# Pro_Micro_Micro_OLED.net
KiCad netlist of a schematic drawn in EAGLE
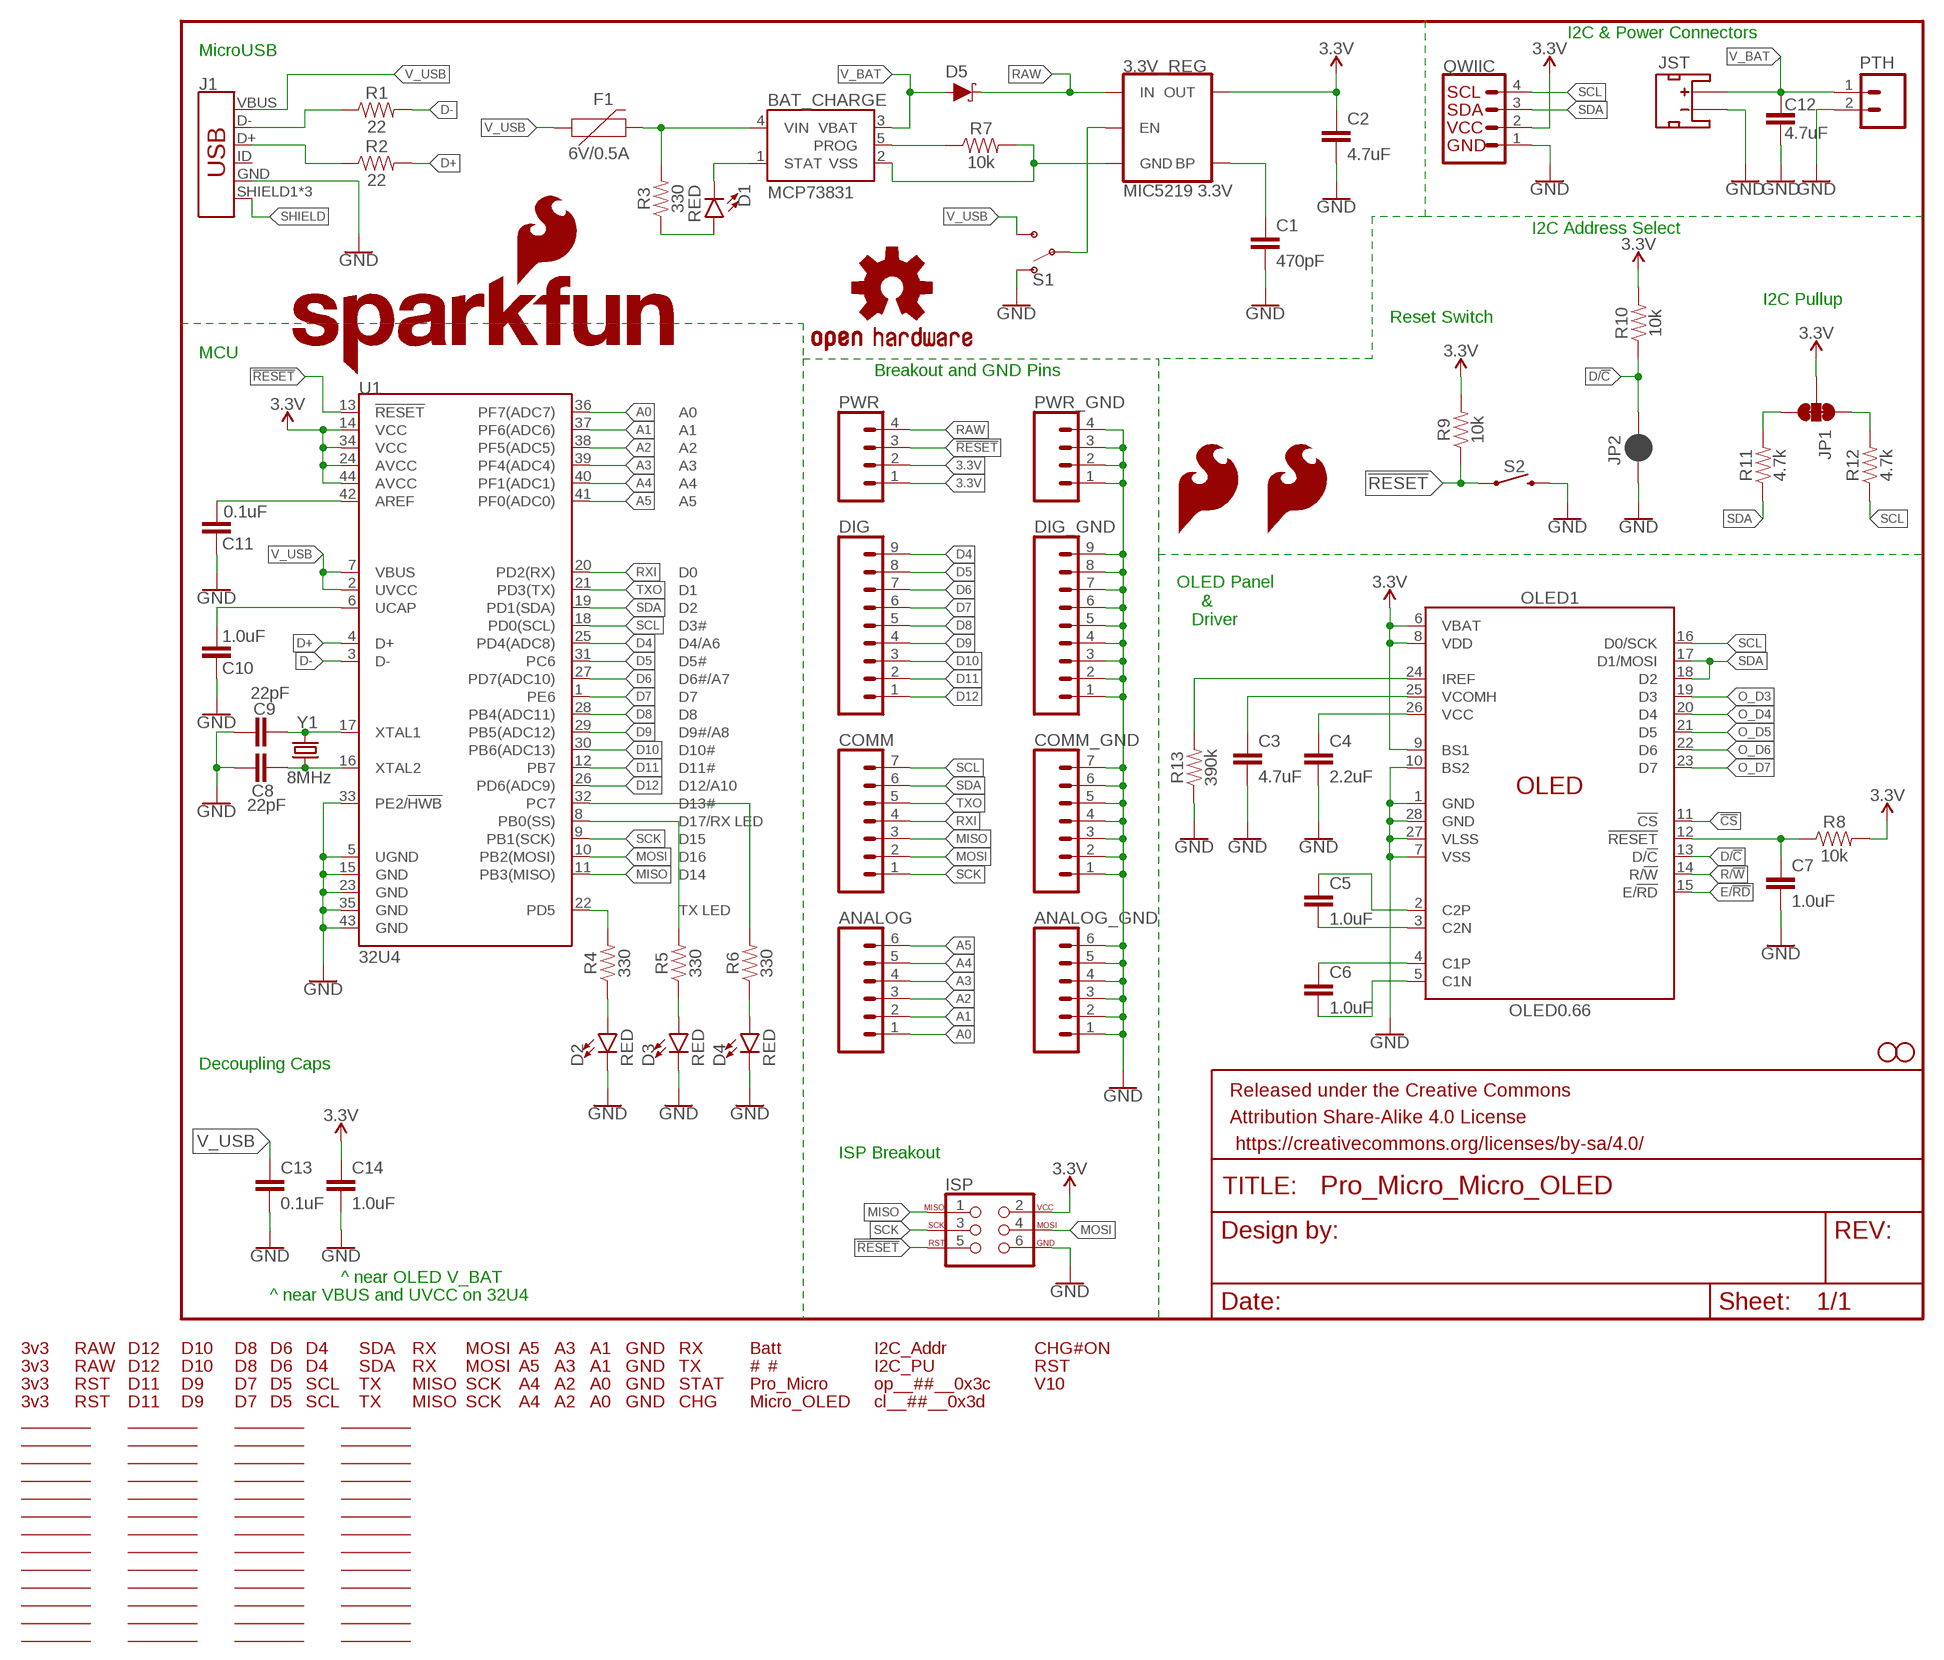
[diagram p0: schematic, sheet 1]

(export (version "E")
  (design (tool "Eeschema 10.0.6"))
  (components
    (comp (ref "3.3V_REG")
      (value "MIC5219 3.3V")
      (footprint "eagle-import:SOT23-5")
      (libsource (lib "eagle-import") (part "V_REG_MIC52193.3V"))
    )
    (comp (ref "ANALOG")
      (value "CONN_06NO_SILK_FEMALE_PTH")
      (footprint "eagle-import:1X06_NO_SILK")
      (libsource (lib "eagle-import") (part "CONN_06NO_SILK_FEMALE_PTH"))
    )
    (comp (ref "ANALOG_GND")
      (value "CONN_06NO_SILK_FEMALE_PTH")
      (footprint "eagle-import:1X06_NO_SILK")
      (libsource (lib "eagle-import") (part "CONN_06NO_SILK_FEMALE_PTH"))
    )
    (comp (ref "BAT_CHARGE")
      (value "MCP73831")
      (footprint "eagle-import:SOT23-5")
      (libsource (lib "eagle-import") (part "MCP73831"))
    )
    (comp (ref "C1")
      (value "470pF")
      (footprint "eagle-import:0603")
      (libsource (lib "eagle-import") (part "470PF-0603-50V-5%"))
    )
    (comp (ref "C2")
      (value "4.7uF")
      (footprint "eagle-import:1206")
      (libsource (lib "eagle-import") (part "4.7UF-1206-16V-(+80/-20%)"))
    )
    (comp (ref "C3")
      (value "4.7uF")
      (footprint "eagle-import:1206")
      (libsource (lib "eagle-import") (part "4.7UF-1206-16V-(+80/-20%)"))
    )
    (comp (ref "C4")
      (value "2.2uF")
      (footprint "eagle-import:0805")
      (libsource (lib "eagle-import") (part "2.2UF-0805-25V-(+80/-20%)"))
    )
    (comp (ref "C5")
      (value "1.0uF")
      (footprint "eagle-import:0805")
      (libsource (lib "eagle-import") (part "1.0UF-0805-25V-10%"))
    )
    (comp (ref "C6")
      (value "1.0uF")
      (footprint "eagle-import:0805")
      (libsource (lib "eagle-import") (part "1.0UF-0805-25V-10%"))
    )
    (comp (ref "C7")
      (value "1.0uF")
      (footprint "eagle-import:0603")
      (libsource (lib "eagle-import") (part "1.0UF-0603-16V-10%"))
    )
    (comp (ref "C8")
      (value "22pF")
      (footprint "eagle-import:0603")
      (libsource (lib "eagle-import") (part "22PF-0603-50V-5%"))
    )
    (comp (ref "C9")
      (value "22pF")
      (footprint "eagle-import:0603")
      (libsource (lib "eagle-import") (part "22PF-0603-50V-5%"))
    )
    (comp (ref "C10")
      (value "1.0uF")
      (footprint "eagle-import:0603")
      (libsource (lib "eagle-import") (part "1.0UF-0603-16V-10%"))
    )
    (comp (ref "C11")
      (value "0.1uF")
      (footprint "eagle-import:0603")
      (libsource (lib "eagle-import") (part "0.1UF-0603-25V-(+80/-20%)"))
    )
    (comp (ref "C12")
      (value "4.7uF")
      (footprint "eagle-import:1206")
      (libsource (lib "eagle-import") (part "4.7UF-1206-16V-(+80/-20%)"))
    )
    (comp (ref "C13")
      (value "0.1uF")
      (footprint "eagle-import:0603")
      (libsource (lib "eagle-import") (part "0.1UF-0603-25V-(+80/-20%)"))
    )
    (comp (ref "C14")
      (value "1.0uF")
      (footprint "eagle-import:0603")
      (libsource (lib "eagle-import") (part "1.0UF-0603-16V-10%"))
    )
    (comp (ref "COMM")
      (value "CONN_07NO_SILK")
      (footprint "eagle-import:1X07_NO_SILK")
      (libsource (lib "eagle-import") (part "CONN_07NO_SILK"))
    )
    (comp (ref "COMM_GND")
      (value "CONN_07NO_SILK")
      (footprint "eagle-import:1X07_NO_SILK")
      (libsource (lib "eagle-import") (part "CONN_07NO_SILK"))
    )
    (comp (ref "D1")
      (value "RED")
      (footprint "eagle-import:LED-0603")
      (libsource (lib "eagle-import") (part "LED-RED0603"))
    )
    (comp (ref "D2")
      (value "RED")
      (footprint "eagle-import:LED-0603")
      (libsource (lib "eagle-import") (part "LED-RED0603"))
    )
    (comp (ref "D3")
      (value "RED")
      (footprint "eagle-import:LED-0603")
      (libsource (lib "eagle-import") (part "LED-RED0603"))
    )
    (comp (ref "D4")
      (value "RED")
      (footprint "eagle-import:LED-0603")
      (libsource (lib "eagle-import") (part "LED-RED0603"))
    )
    (comp (ref "D5")
      (value "3A/40V/500mV")
      (footprint "eagle-import:SMA-DIODE")
      (libsource (lib "eagle-import") (part "DIODE-SCHOTTKY-B340A"))
    )
    (comp (ref "DIG")
      (value "CONN_09NO_SILK")
      (footprint "eagle-import:1X09_NO_SILK")
      (libsource (lib "eagle-import") (part "CONN_09NO_SILK"))
    )
    (comp (ref "DIG_GND")
      (value "CONN_09NO_SILK")
      (footprint "eagle-import:1X09_NO_SILK")
      (libsource (lib "eagle-import") (part "CONN_09NO_SILK"))
    )
    (comp (ref "F1")
      (value "6V/0.5A")
      (footprint "eagle-import:1206")
      (libsource (lib "eagle-import") (part "PPTC_HALF-AMP"))
    )
    (comp (ref "FRAME1")
      (value "FRAME-LETTER")
      (footprint "eagle-import:CREATIVE_COMMONS")
      (libsource (lib "eagle-import") (part "FRAME-LETTER"))
    )
    (comp (ref "H1")
      (value "STAND-OFF")
      (footprint "eagle-import:STAND-OFF")
      (libsource (lib "eagle-import") (part "STAND-OFF"))
    )
    (comp (ref "H2")
      (value "STAND-OFF")
      (footprint "eagle-import:STAND-OFF")
      (libsource (lib "eagle-import") (part "STAND-OFF"))
    )
    (comp (ref "ISP")
      (value "AVR_SPI_PROG_3X2TESTPOINTS")
      (footprint "eagle-import:2X3_TEST_POINTS")
      (libsource (lib "eagle-import") (part "AVR_SPI_PROG_3X2TESTPOINTS"))
    )
    (comp (ref "J1")
      (value "USB_MICRO-BREDUCED_PASTE")
      (footprint "eagle-import:USB-B-MICRO-SMD_RED_PASTE")
      (libsource (lib "eagle-import") (part "USB_MICRO-BREDUCED_PASTE"))
    )
    (comp (ref "JP1")
      (value "JUMPER-SMT_3_2-NC_TRACE_SILK")
      (footprint "eagle-import:SMT-JUMPER_3_2-NC_TRACE_SILK")
      (libsource (lib "eagle-import") (part "JUMPER-SMT_3_2-NC_TRACE_SILK"))
    )
    (comp (ref "JP2")
      (value "JUMPER-SMT_2_NC_PASTE_SILK")
      (footprint "eagle-import:SMT-JUMPER_2_NC_PASTE_SILK")
      (libsource (lib "eagle-import") (part "JUMPER-SMT_2_NC_PASTE_SILK"))
    )
    (comp (ref "JST")
      (value "JST_2MM_MALE")
      (footprint "eagle-import:JST-2-SMD")
      (libsource (lib "eagle-import") (part "JST_2MM_MALE"))
    )
    (comp (ref "LOGO1")
      (value "SFE_LOGO_NAME_FLAME.2_INCH")
      (footprint "eagle-import:SFE_LOGO_NAME_FLAME_.2")
      (libsource (lib "eagle-import") (part "SFE_LOGO_NAME_FLAME.2_INCH"))
    )
    (comp (ref "LOGO2")
      (value "OSHW-LOGOS-COPPER")
      (footprint "eagle-import:OSHW-LOGO-S_COPPER")
      (libsource (lib "eagle-import") (part "OSHW-LOGOS-COPPER"))
    )
    (comp (ref "LOGO3")
      (value "SFE_LOGO_FLAME.1COP")
      (footprint "eagle-import:SFE_LOGO_FLAME_COPPER_.1")
      (libsource (lib "eagle-import") (part "SFE_LOGO_FLAME.1COP"))
    )
    (comp (ref "LOGO4")
      (value "SFE_LOGO_FLAME.1_INCH")
      (footprint "eagle-import:SFE_LOGO_FLAME_.1")
      (libsource (lib "eagle-import") (part "SFE_LOGO_FLAME.1_INCH"))
    )
    (comp (ref "OLED1")
      (value "OLED0.66")
      (footprint "eagle-import:OLED-0.66-64X48")
      (libsource (lib "eagle-import") (part "OLED0.66"))
    )
    (comp (ref "PTH")
      (value "CONN_021X02_NO_SILK")
      (footprint "eagle-import:1X02_NO_SILK")
      (libsource (lib "eagle-import") (part "CONN_021X02_NO_SILK"))
    )
    (comp (ref "PWR")
      (value "CONN_041X04_NO_SILK")
      (footprint "eagle-import:1X04_NO_SILK")
      (libsource (lib "eagle-import") (part "CONN_041X04_NO_SILK"))
    )
    (comp (ref "PWR_GND")
      (value "CONN_041X04_NO_SILK")
      (footprint "eagle-import:1X04_NO_SILK")
      (libsource (lib "eagle-import") (part "CONN_041X04_NO_SILK"))
    )
    (comp (ref "QWIIC")
      (value "QWIIC_CONNECTORJS-1MM")
      (footprint "eagle-import:1X04_1MM_RA")
      (libsource (lib "eagle-import") (part "QWIIC_CONNECTORJS-1MM"))
    )
    (comp (ref "R1")
      (value "22")
      (footprint "eagle-import:0603")
      (libsource (lib "eagle-import") (part "22OHM-0603-1/10W-1%"))
    )
    (comp (ref "R2")
      (value "22")
      (footprint "eagle-import:0603")
      (libsource (lib "eagle-import") (part "22OHM-0603-1/10W-1%"))
    )
    (comp (ref "R3")
      (value "330")
      (footprint "eagle-import:0603")
      (libsource (lib "eagle-import") (part "330OHM-0603-1/10W-1%"))
    )
    (comp (ref "R4")
      (value "330")
      (footprint "eagle-import:0603")
      (libsource (lib "eagle-import") (part "330OHM-0603-1/10W-1%"))
    )
    (comp (ref "R5")
      (value "330")
      (footprint "eagle-import:0603")
      (libsource (lib "eagle-import") (part "330OHM-0603-1/10W-1%"))
    )
    (comp (ref "R6")
      (value "330")
      (footprint "eagle-import:0603")
      (libsource (lib "eagle-import") (part "330OHM-0603-1/10W-1%"))
    )
    (comp (ref "R7")
      (value "10k")
      (footprint "eagle-import:0603")
      (libsource (lib "eagle-import") (part "10KOHM-0603-1/10W-1%"))
    )
    (comp (ref "R8")
      (value "10k")
      (footprint "eagle-import:0603")
      (libsource (lib "eagle-import") (part "10KOHM-0603-1/10W-1%"))
    )
    (comp (ref "R9")
      (value "10k")
      (footprint "eagle-import:0603")
      (libsource (lib "eagle-import") (part "10KOHM-0603-1/10W-1%"))
    )
    (comp (ref "R10")
      (value "10k")
      (footprint "eagle-import:0603")
      (libsource (lib "eagle-import") (part "10KOHM-0603-1/10W-1%"))
    )
    (comp (ref "R11")
      (value "4.7k")
      (footprint "eagle-import:0603")
      (libsource (lib "eagle-import") (part "4.7KOHM-0603-1/10W-1%"))
    )
    (comp (ref "R12")
      (value "4.7k")
      (footprint "eagle-import:0603")
      (libsource (lib "eagle-import") (part "4.7KOHM-0603-1/10W-1%"))
    )
    (comp (ref "R13")
      (value "390k")
      (footprint "eagle-import:0603")
      (libsource (lib "eagle-import") (part "390KOHM-0603-1/10W-1%"))
    )
    (comp (ref "S1")
      (value "SWITCH-SPDT-SMD-RIGHT-ANGLE")
      (footprint "eagle-import:SWITCH_SPST_SMD_A")
      (libsource (lib "eagle-import") (part "SWITCH-SPDT-SMD-RIGHT-ANGLE"))
    )
    (comp (ref "S2")
      (value "MOMENTARY-SWITCH-SPST-SMD-4.6X2.8MM")
      (footprint "eagle-import:TACTILE_SWITCH_SMD_4.6X2.8MM")
      (libsource (lib "eagle-import") (part "MOMENTARY-SWITCH-SPST-SMD-4.6X2.8MM"))
    )
    (comp (ref "U$1")
      (value "3V317")
      (footprint "eagle-import:3V317")
      (libsource (lib "eagle-import") (part "3V317"))
    )
    (comp (ref "U$2")
      (value "3V317")
      (footprint "eagle-import:3V317")
      (libsource (lib "eagle-import") (part "3V317"))
    )
    (comp (ref "U$3")
      (value "3V317")
      (footprint "eagle-import:3V317")
      (libsource (lib "eagle-import") (part "3V317"))
    )
    (comp (ref "U$4")
      (value "3V317")
      (footprint "eagle-import:3V317")
      (libsource (lib "eagle-import") (part "3V317"))
    )
    (comp (ref "U$5")
      (value "RAW15")
      (footprint "eagle-import:RAW15")
      (libsource (lib "eagle-import") (part "RAW15"))
    )
    (comp (ref "U$6")
      (value "RAW15")
      (footprint "eagle-import:RAW15")
      (libsource (lib "eagle-import") (part "RAW15"))
    )
    (comp (ref "U$7")
      (value "RST16")
      (footprint "eagle-import:RST16")
      (libsource (lib "eagle-import") (part "RST16"))
    )
    (comp (ref "U$8")
      (value "RST16")
      (footprint "eagle-import:RST16")
      (libsource (lib "eagle-import") (part "RST16"))
    )
    (comp (ref "U$9")
      (value "D120")
      (footprint "eagle-import:D120")
      (libsource (lib "eagle-import") (part "D120"))
    )
    (comp (ref "U$10")
      (value "D120")
      (footprint "eagle-import:D120")
      (libsource (lib "eagle-import") (part "D120"))
    )
    (comp (ref "U$11")
      (value "D111")
      (footprint "eagle-import:D111")
      (libsource (lib "eagle-import") (part "D111"))
    )
    (comp (ref "U$12")
      (value "D111")
      (footprint "eagle-import:D111")
      (libsource (lib "eagle-import") (part "D111"))
    )
    (comp (ref "U$13")
      (value "D102")
      (footprint "eagle-import:D102")
      (libsource (lib "eagle-import") (part "D102"))
    )
    (comp (ref "U$14")
      (value "D102")
      (footprint "eagle-import:D102")
      (libsource (lib "eagle-import") (part "D102"))
    )
    (comp (ref "U$15")
      (value "D93")
      (footprint "eagle-import:D93")
      (libsource (lib "eagle-import") (part "D93"))
    )
    (comp (ref "U$16")
      (value "D93")
      (footprint "eagle-import:D93")
      (libsource (lib "eagle-import") (part "D93"))
    )
    (comp (ref "U$17")
      (value "D84")
      (footprint "eagle-import:D84")
      (libsource (lib "eagle-import") (part "D84"))
    )
    (comp (ref "U$18")
      (value "D84")
      (footprint "eagle-import:D84")
      (libsource (lib "eagle-import") (part "D84"))
    )
    (comp (ref "U$19")
      (value "D75")
      (footprint "eagle-import:D75")
      (libsource (lib "eagle-import") (part "D75"))
    )
    (comp (ref "U$20")
      (value "D75")
      (footprint "eagle-import:D75")
      (libsource (lib "eagle-import") (part "D75"))
    )
    (comp (ref "U$21")
      (value "D66")
      (footprint "eagle-import:D66")
      (libsource (lib "eagle-import") (part "D66"))
    )
    (comp (ref "U$22")
      (value "D66")
      (footprint "eagle-import:D66")
      (libsource (lib "eagle-import") (part "D66"))
    )
    (comp (ref "U$23")
      (value "D57")
      (footprint "eagle-import:D57")
      (libsource (lib "eagle-import") (part "D57"))
    )
    (comp (ref "U$24")
      (value "D57")
      (footprint "eagle-import:D57")
      (libsource (lib "eagle-import") (part "D57"))
    )
    (comp (ref "U$25")
      (value "D48")
      (footprint "eagle-import:D48")
      (libsource (lib "eagle-import") (part "D48"))
    )
    (comp (ref "U$26")
      (value "D48")
      (footprint "eagle-import:D48")
      (libsource (lib "eagle-import") (part "D48"))
    )
    (comp (ref "U$27")
      (value "SCL18")
      (footprint "eagle-import:SCL18")
      (libsource (lib "eagle-import") (part "SCL18"))
    )
    (comp (ref "U$28")
      (value "SCL18")
      (footprint "eagle-import:SCL18")
      (libsource (lib "eagle-import") (part "SCL18"))
    )
    (comp (ref "U$29")
      (value "SDA19")
      (footprint "eagle-import:SDA19")
      (libsource (lib "eagle-import") (part "SDA19"))
    )
    (comp (ref "U$30")
      (value "SDA19")
      (footprint "eagle-import:SDA19")
      (libsource (lib "eagle-import") (part "SDA19"))
    )
    (comp (ref "U$31")
      (value "TX20")
      (footprint "eagle-import:TX20")
      (libsource (lib "eagle-import") (part "TX20"))
    )
    (comp (ref "U$32")
      (value "TX20")
      (footprint "eagle-import:TX20")
      (libsource (lib "eagle-import") (part "TX20"))
    )
    (comp (ref "U$33")
      (value "RX21")
      (footprint "eagle-import:RX21")
      (libsource (lib "eagle-import") (part "RX21"))
    )
    (comp (ref "U$34")
      (value "RX21")
      (footprint "eagle-import:RX21")
      (libsource (lib "eagle-import") (part "RX21"))
    )
    (comp (ref "U$35")
      (value "MISO22")
      (footprint "eagle-import:MISO22")
      (libsource (lib "eagle-import") (part "MISO22"))
    )
    (comp (ref "U$36")
      (value "MISO22")
      (footprint "eagle-import:MISO22")
      (libsource (lib "eagle-import") (part "MISO22"))
    )
    (comp (ref "U$37")
      (value "MOSI28")
      (footprint "eagle-import:MOSI28")
      (libsource (lib "eagle-import") (part "MOSI28"))
    )
    (comp (ref "U$38")
      (value "MOSI28")
      (footprint "eagle-import:MOSI28")
      (libsource (lib "eagle-import") (part "MOSI28"))
    )
    (comp (ref "U$39")
      (value "SCK23")
      (footprint "eagle-import:SCK23")
      (libsource (lib "eagle-import") (part "SCK23"))
    )
    (comp (ref "U$40")
      (value "SCK23")
      (footprint "eagle-import:SCK23")
      (libsource (lib "eagle-import") (part "SCK23"))
    )
    (comp (ref "U$41")
      (value "A59")
      (footprint "eagle-import:A59")
      (libsource (lib "eagle-import") (part "A59"))
    )
    (comp (ref "U$42")
      (value "A59")
      (footprint "eagle-import:A59")
      (libsource (lib "eagle-import") (part "A59"))
    )
    (comp (ref "U$43")
      (value "A410")
      (footprint "eagle-import:A410")
      (libsource (lib "eagle-import") (part "A410"))
    )
    (comp (ref "U$44")
      (value "A410")
      (footprint "eagle-import:A410")
      (libsource (lib "eagle-import") (part "A410"))
    )
    (comp (ref "U$45")
      (value "A311")
      (footprint "eagle-import:A311")
      (libsource (lib "eagle-import") (part "A311"))
    )
    (comp (ref "U$46")
      (value "A311")
      (footprint "eagle-import:A311")
      (libsource (lib "eagle-import") (part "A311"))
    )
    (comp (ref "U$47")
      (value "A212")
      (footprint "eagle-import:A212")
      (libsource (lib "eagle-import") (part "A212"))
    )
    (comp (ref "U$48")
      (value "A212")
      (footprint "eagle-import:A212")
      (libsource (lib "eagle-import") (part "A212"))
    )
    (comp (ref "U$49")
      (value "A113")
      (footprint "eagle-import:A113")
      (libsource (lib "eagle-import") (part "A113"))
    )
    (comp (ref "U$50")
      (value "A113")
      (footprint "eagle-import:A113")
      (libsource (lib "eagle-import") (part "A113"))
    )
    (comp (ref "U$51")
      (value "A014")
      (footprint "eagle-import:A014")
      (libsource (lib "eagle-import") (part "A014"))
    )
    (comp (ref "U$52")
      (value "A014")
      (footprint "eagle-import:A014")
      (libsource (lib "eagle-import") (part "A014"))
    )
    (comp (ref "U$53")
      (value "GND38")
      (footprint "eagle-import:GND38")
      (libsource (lib "eagle-import") (part "GND38"))
    )
    (comp (ref "U$54")
      (value "GND38")
      (footprint "eagle-import:GND38")
      (libsource (lib "eagle-import") (part "GND38"))
    )
    (comp (ref "U$55")
      (value "GND39")
      (footprint "eagle-import:GND39")
      (libsource (lib "eagle-import") (part "GND39"))
    )
    (comp (ref "U$56")
      (value "GND39")
      (footprint "eagle-import:GND39")
      (libsource (lib "eagle-import") (part "GND39"))
    )
    (comp (ref "U$57")
      (value "RX36")
      (footprint "eagle-import:RX36")
      (libsource (lib "eagle-import") (part "RX36"))
    )
    (comp (ref "U$58")
      (value "TX34")
      (footprint "eagle-import:TX34")
      (libsource (lib "eagle-import") (part "TX34"))
    )
    (comp (ref "U$59")
      (value "STAT35")
      (footprint "eagle-import:STAT35")
      (libsource (lib "eagle-import") (part "STAT35"))
    )
    (comp (ref "U$60")
      (value "CHG30")
      (footprint "eagle-import:CHG30")
      (libsource (lib "eagle-import") (part "CHG30"))
    )
    (comp (ref "U$61")
      (value "BATT29")
      (footprint "eagle-import:BATT29")
      (libsource (lib "eagle-import") (part "BATT29"))
    )
    (comp (ref "U$62")
      (value "#32")
      (footprint "eagle-import:#32")
      (libsource (lib "eagle-import") (part "#32"))
    )
    (comp (ref "U$63")
      (value "#31")
      (footprint "eagle-import:#31")
      (libsource (lib "eagle-import") (part "#31"))
    )
    (comp (ref "U$64")
      (value "PRO_MICRO43")
      (footprint "eagle-import:PRO_MICRO43")
      (libsource (lib "eagle-import") (part "PRO_MICRO43"))
    )
    (comp (ref "U$65")
      (value "MICRO_OLED42")
      (footprint "eagle-import:MICRO_OLED42")
      (libsource (lib "eagle-import") (part "MICRO_OLED42"))
    )
    (comp (ref "U$66")
      (value "_______39")
      (footprint "eagle-import:_______39")
      (libsource (lib "eagle-import") (part "_______39"))
    )
    (comp (ref "U$67")
      (value "_______39")
      (footprint "eagle-import:_______39")
      (libsource (lib "eagle-import") (part "_______39"))
    )
    (comp (ref "U$68")
      (value "_______39")
      (footprint "eagle-import:_______39")
      (libsource (lib "eagle-import") (part "_______39"))
    )
    (comp (ref "U$69")
      (value "_______39")
      (footprint "eagle-import:_______39")
      (libsource (lib "eagle-import") (part "_______39"))
    )
    (comp (ref "U$70")
      (value "_______39")
      (footprint "eagle-import:_______39")
      (libsource (lib "eagle-import") (part "_______39"))
    )
    (comp (ref "U$71")
      (value "_______39")
      (footprint "eagle-import:_______39")
      (libsource (lib "eagle-import") (part "_______39"))
    )
    (comp (ref "U$72")
      (value "_______39")
      (footprint "eagle-import:_______39")
      (libsource (lib "eagle-import") (part "_______39"))
    )
    (comp (ref "U$73")
      (value "_______39")
      (footprint "eagle-import:_______39")
      (libsource (lib "eagle-import") (part "_______39"))
    )
    (comp (ref "U$74")
      (value "_______39")
      (footprint "eagle-import:_______39")
      (libsource (lib "eagle-import") (part "_______39"))
    )
    (comp (ref "U$75")
      (value "_______39")
      (footprint "eagle-import:_______39")
      (libsource (lib "eagle-import") (part "_______39"))
    )
    (comp (ref "U$76")
      (value "_______39")
      (footprint "eagle-import:_______39")
      (libsource (lib "eagle-import") (part "_______39"))
    )
    (comp (ref "U$77")
      (value "_______39")
      (footprint "eagle-import:_______39")
      (libsource (lib "eagle-import") (part "_______39"))
    )
    (comp (ref "U$78")
      (value "_______39")
      (footprint "eagle-import:_______39")
      (libsource (lib "eagle-import") (part "_______39"))
    )
    (comp (ref "U$79")
      (value "_______39")
      (footprint "eagle-import:_______39")
      (libsource (lib "eagle-import") (part "_______39"))
    )
    (comp (ref "U$80")
      (value "_______39")
      (footprint "eagle-import:_______39")
      (libsource (lib "eagle-import") (part "_______39"))
    )
    (comp (ref "U$81")
      (value "_______39")
      (footprint "eagle-import:_______39")
      (libsource (lib "eagle-import") (part "_______39"))
    )
    (comp (ref "U$82")
      (value "_______39")
      (footprint "eagle-import:_______39")
      (libsource (lib "eagle-import") (part "_______39"))
    )
    (comp (ref "U$83")
      (value "_______39")
      (footprint "eagle-import:_______39")
      (libsource (lib "eagle-import") (part "_______39"))
    )
    (comp (ref "U$84")
      (value "_______39")
      (footprint "eagle-import:_______39")
      (libsource (lib "eagle-import") (part "_______39"))
    )
    (comp (ref "U$85")
      (value "_______39")
      (footprint "eagle-import:_______39")
      (libsource (lib "eagle-import") (part "_______39"))
    )
    (comp (ref "U$86")
      (value "_______39")
      (footprint "eagle-import:_______39")
      (libsource (lib "eagle-import") (part "_______39"))
    )
    (comp (ref "U$87")
      (value "_______39")
      (footprint "eagle-import:_______39")
      (libsource (lib "eagle-import") (part "_______39"))
    )
    (comp (ref "U$88")
      (value "_______39")
      (footprint "eagle-import:_______39")
      (libsource (lib "eagle-import") (part "_______39"))
    )
    (comp (ref "U$89")
      (value "_______39")
      (footprint "eagle-import:_______39")
      (libsource (lib "eagle-import") (part "_______39"))
    )
    (comp (ref "U$90")
      (value "_______39")
      (footprint "eagle-import:_______39")
      (libsource (lib "eagle-import") (part "_______39"))
    )
    (comp (ref "U$91")
      (value "_______39")
      (footprint "eagle-import:_______39")
      (libsource (lib "eagle-import") (part "_______39"))
    )
    (comp (ref "U$92")
      (value "_______39")
      (footprint "eagle-import:_______39")
      (libsource (lib "eagle-import") (part "_______39"))
    )
    (comp (ref "U$93")
      (value "_______39")
      (footprint "eagle-import:_______39")
      (libsource (lib "eagle-import") (part "_______39"))
    )
    (comp (ref "U$94")
      (value "_______39")
      (footprint "eagle-import:_______39")
      (libsource (lib "eagle-import") (part "_______39"))
    )
    (comp (ref "U$95")
      (value "_______39")
      (footprint "eagle-import:_______39")
      (libsource (lib "eagle-import") (part "_______39"))
    )
    (comp (ref "U$96")
      (value "_______39")
      (footprint "eagle-import:_______39")
      (libsource (lib "eagle-import") (part "_______39"))
    )
    (comp (ref "U$97")
      (value "_______39")
      (footprint "eagle-import:_______39")
      (libsource (lib "eagle-import") (part "_______39"))
    )
    (comp (ref "U$98")
      (value "_______39")
      (footprint "eagle-import:_______39")
      (libsource (lib "eagle-import") (part "_______39"))
    )
    (comp (ref "U$99")
      (value "_______39")
      (footprint "eagle-import:_______39")
      (libsource (lib "eagle-import") (part "_______39"))
    )
    (comp (ref "U$100")
      (value "_______39")
      (footprint "eagle-import:_______39")
      (libsource (lib "eagle-import") (part "_______39"))
    )
    (comp (ref "U$101")
      (value "_______39")
      (footprint "eagle-import:_______39")
      (libsource (lib "eagle-import") (part "_______39"))
    )
    (comp (ref "U$102")
      (value "_______39")
      (footprint "eagle-import:_______39")
      (libsource (lib "eagle-import") (part "_______39"))
    )
    (comp (ref "U$103")
      (value "_______39")
      (footprint "eagle-import:_______39")
      (libsource (lib "eagle-import") (part "_______39"))
    )
    (comp (ref "U$104")
      (value "_______39")
      (footprint "eagle-import:_______39")
      (libsource (lib "eagle-import") (part "_______39"))
    )
    (comp (ref "U$105")
      (value "_______39")
      (footprint "eagle-import:_______39")
      (libsource (lib "eagle-import") (part "_______39"))
    )
    (comp (ref "U$106")
      (value "_______39")
      (footprint "eagle-import:_______39")
      (libsource (lib "eagle-import") (part "_______39"))
    )
    (comp (ref "U$107")
      (value "_______39")
      (footprint "eagle-import:_______39")
      (libsource (lib "eagle-import") (part "_______39"))
    )
    (comp (ref "U$108")
      (value "_______39")
      (footprint "eagle-import:_______39")
      (libsource (lib "eagle-import") (part "_______39"))
    )
    (comp (ref "U$109")
      (value "_______39")
      (footprint "eagle-import:_______39")
      (libsource (lib "eagle-import") (part "_______39"))
    )
    (comp (ref "U$110")
      (value "_______39")
      (footprint "eagle-import:_______39")
      (libsource (lib "eagle-import") (part "_______39"))
    )
    (comp (ref "U$111")
      (value "_______39")
      (footprint "eagle-import:_______39")
      (libsource (lib "eagle-import") (part "_______39"))
    )
    (comp (ref "U$112")
      (value "_______39")
      (footprint "eagle-import:_______39")
      (libsource (lib "eagle-import") (part "_______39"))
    )
    (comp (ref "U$113")
      (value "_______39")
      (footprint "eagle-import:_______39")
      (libsource (lib "eagle-import") (part "_______39"))
    )
    (comp (ref "U$114")
      (value "_______39")
      (footprint "eagle-import:_______39")
      (libsource (lib "eagle-import") (part "_______39"))
    )
    (comp (ref "U$115")
      (value "_______39")
      (footprint "eagle-import:_______39")
      (libsource (lib "eagle-import") (part "_______39"))
    )
    (comp (ref "U$116")
      (value "_______39")
      (footprint "eagle-import:_______39")
      (libsource (lib "eagle-import") (part "_______39"))
    )
    (comp (ref "U$117")
      (value "_______39")
      (footprint "eagle-import:_______39")
      (libsource (lib "eagle-import") (part "_______39"))
    )
    (comp (ref "U$118")
      (value "I2C_ADDR40")
      (footprint "eagle-import:I2C_ADDR40")
      (libsource (lib "eagle-import") (part "I2C_ADDR40"))
    )
    (comp (ref "U$119")
      (value "I2C_PU39")
      (footprint "eagle-import:I2C_PU39")
      (libsource (lib "eagle-import") (part "I2C_PU39"))
    )
    (comp (ref "U$120")
      (value "OP__##__0X3C42")
      (footprint "eagle-import:OP__##__0X3C42")
      (libsource (lib "eagle-import") (part "OP__##__0X3C42"))
    )
    (comp (ref "U$121")
      (value "CL__##__0X3D41")
      (footprint "eagle-import:CL__##__0X3D41")
      (libsource (lib "eagle-import") (part "CL__##__0X3D41"))
    )
    (comp (ref "U$122")
      (value "CHG#ON41")
      (footprint "eagle-import:CHG#ON41")
      (libsource (lib "eagle-import") (part "CHG#ON41"))
    )
    (comp (ref "U$123")
      (value "RST16")
      (footprint "eagle-import:RST16")
      (libsource (lib "eagle-import") (part "RST16"))
    )
    (comp (ref "U$124")
      (value "V1044")
      (footprint "eagle-import:V1044")
      (libsource (lib "eagle-import") (part "V1044"))
    )
    (comp (ref "U1")
      (value "32U4")
      (footprint "eagle-import:QFN-44-NOPAD_1_1")
      (libsource (lib "eagle-import") (part "ATMEGA32U41{colon}1"))
    )
    (comp (ref "Y1")
      (value "8MHz")
      (footprint "eagle-import:CRYSTAL-SMD-5X3.2-4PAD")
      (libsource (lib "eagle-import") (part "CRYSTAL-8MHZSMD-5X3.2"))
    )
  )
  (nets
    (net (code "1") (name "/D{slash}~{C}") (class "Default")
      (node (ref "JP2") (pin "2") (pinfunction "2_2") (pintype "passive"))
      (node (ref "OLED1") (pin "13") (pinfunction "D/~{C}_13") (pintype "bidirectional"))
      (node (ref "R10") (pin "1") (pinfunction "1_1") (pintype "passive"))
    )
    (net (code "2") (name "/E{slash}~{RD}") (class "Default")
      (node (ref "OLED1") (pin "15") (pinfunction "E/~{RD}_15") (pintype "bidirectional"))
    )
    (net (code "3") (name "/R{slash}~{W}") (class "Default")
      (node (ref "OLED1") (pin "14") (pinfunction "R/~{W}_14") (pintype "bidirectional"))
    )
    (net (code "4") (name "/~{CS}") (class "Default")
      (node (ref "OLED1") (pin "11") (pinfunction "~{CS}_11") (pintype "bidirectional"))
    )
    (net (code "5") (name "/~{RESET}") (class "Default")
      (node (ref "ISP") (pin "5") (pinfunction "5_5") (pintype "passive"))
      (node (ref "PWR") (pin "3") (pinfunction "3_3") (pintype "passive"))
      (node (ref "R9") (pin "1") (pinfunction "1_1") (pintype "passive"))
      (node (ref "S2") (pin "1") (pinfunction "1_1") (pintype "passive"))
      (node (ref "S2") (pin "2") (pinfunction "1_2") (pintype "passive"))
      (node (ref "U1") (pin "13") (pinfunction "~{RESET}_13") (pintype "bidirectional"))
    )
    (net (code "6") (name "3.3V") (class "Default")
      (node (ref "3.3V_REG") (pin "5") (pinfunction "OUT_5") (pintype "passive"))
      (node (ref "C14") (pin "1") (pinfunction "1_1") (pintype "passive"))
      (node (ref "C2") (pin "1") (pinfunction "1_1") (pintype "passive"))
      (node (ref "ISP") (pin "2") (pinfunction "2_2") (pintype "passive"))
      (node (ref "JP1") (pin "2") (pinfunction "2_2") (pintype "passive"))
      (node (ref "OLED1") (pin "6") (pinfunction "VBAT_6") (pintype "bidirectional"))
      (node (ref "OLED1") (pin "8") (pinfunction "VDD_8") (pintype "bidirectional"))
      (node (ref "OLED1") (pin "9") (pinfunction "BS1_9") (pintype "bidirectional"))
      (node (ref "PWR") (pin "1") (pinfunction "1_1") (pintype "passive"))
      (node (ref "PWR") (pin "2") (pinfunction "2_2") (pintype "passive"))
      (node (ref "QWIIC") (pin "2") (pinfunction "2_2") (pintype "power_in"))
      (node (ref "R10") (pin "2") (pinfunction "2_2") (pintype "passive"))
      (node (ref "R8") (pin "2") (pinfunction "2_2") (pintype "passive"))
      (node (ref "R9") (pin "2") (pinfunction "2_2") (pintype "passive"))
      (node (ref "U1") (pin "14") (pinfunction "VCC_14") (pintype "bidirectional"))
      (node (ref "U1") (pin "24") (pinfunction "AVCC_24") (pintype "bidirectional"))
      (node (ref "U1") (pin "34") (pinfunction "VCC_34") (pintype "bidirectional"))
      (node (ref "U1") (pin "44") (pinfunction "AVCC_44") (pintype "bidirectional"))
    )
    (net (code "7") (name "A0") (class "Default")
      (node (ref "ANALOG") (pin "1") (pinfunction "1_1") (pintype "passive"))
      (node (ref "U1") (pin "36") (pinfunction "PF7(ADC7)_36") (pintype "bidirectional"))
    )
    (net (code "8") (name "A1") (class "Default")
      (node (ref "ANALOG") (pin "2") (pinfunction "2_2") (pintype "passive"))
      (node (ref "U1") (pin "37") (pinfunction "PF6(ADC6)_37") (pintype "bidirectional"))
    )
    (net (code "9") (name "A2") (class "Default")
      (node (ref "ANALOG") (pin "3") (pinfunction "3_3") (pintype "passive"))
      (node (ref "U1") (pin "38") (pinfunction "PF5(ADC5)_38") (pintype "bidirectional"))
    )
    (net (code "10") (name "A3") (class "Default")
      (node (ref "ANALOG") (pin "4") (pinfunction "4_4") (pintype "passive"))
      (node (ref "U1") (pin "39") (pinfunction "PF4(ADC4)_39") (pintype "bidirectional"))
    )
    (net (code "11") (name "A4") (class "Default")
      (node (ref "ANALOG") (pin "5") (pinfunction "5_5") (pintype "passive"))
      (node (ref "U1") (pin "40") (pinfunction "PF1(ADC1)_40") (pintype "bidirectional"))
    )
    (net (code "12") (name "A5") (class "Default")
      (node (ref "ANALOG") (pin "6") (pinfunction "6_6") (pintype "passive"))
      (node (ref "U1") (pin "41") (pinfunction "PF0(ADC0)_41") (pintype "bidirectional"))
    )
    (net (code "13") (name "D+") (class "Default")
      (node (ref "R2") (pin "2") (pinfunction "2_2") (pintype "passive"))
      (node (ref "U1") (pin "4") (pinfunction "D+_4") (pintype "bidirectional"))
    )
    (net (code "14") (name "D-") (class "Default")
      (node (ref "R1") (pin "2") (pinfunction "2_2") (pintype "passive"))
      (node (ref "U1") (pin "3") (pinfunction "D-_3") (pintype "bidirectional"))
    )
    (net (code "15") (name "D4") (class "Default")
      (node (ref "DIG") (pin "9") (pinfunction "9_9") (pintype "passive"))
      (node (ref "U1") (pin "25") (pinfunction "PD4(ADC8)_25") (pintype "bidirectional"))
    )
    (net (code "16") (name "D5") (class "Default")
      (node (ref "DIG") (pin "8") (pinfunction "8_8") (pintype "passive"))
      (node (ref "U1") (pin "31") (pinfunction "PC6_31") (pintype "bidirectional"))
    )
    (net (code "17") (name "D6") (class "Default")
      (node (ref "DIG") (pin "7") (pinfunction "7_7") (pintype "passive"))
      (node (ref "U1") (pin "27") (pinfunction "PD7(ADC10)_27") (pintype "bidirectional"))
    )
    (net (code "18") (name "D7") (class "Default")
      (node (ref "DIG") (pin "6") (pinfunction "6_6") (pintype "passive"))
      (node (ref "U1") (pin "1") (pinfunction "PE6_1") (pintype "bidirectional"))
    )
    (net (code "19") (name "D8") (class "Default")
      (node (ref "DIG") (pin "5") (pinfunction "5_5") (pintype "passive"))
      (node (ref "U1") (pin "28") (pinfunction "PB4(ADC11)_28") (pintype "bidirectional"))
    )
    (net (code "20") (name "D9") (class "Default")
      (node (ref "DIG") (pin "4") (pinfunction "4_4") (pintype "passive"))
      (node (ref "U1") (pin "29") (pinfunction "PB5(ADC12)_29") (pintype "bidirectional"))
    )
    (net (code "21") (name "D10") (class "Default")
      (node (ref "DIG") (pin "3") (pinfunction "3_3") (pintype "passive"))
      (node (ref "U1") (pin "30") (pinfunction "PB6(ADC13)_30") (pintype "bidirectional"))
    )
    (net (code "22") (name "D11") (class "Default")
      (node (ref "DIG") (pin "2") (pinfunction "2_2") (pintype "passive"))
      (node (ref "U1") (pin "12") (pinfunction "PB7_12") (pintype "bidirectional"))
    )
    (net (code "23") (name "D12") (class "Default")
      (node (ref "DIG") (pin "1") (pinfunction "1_1") (pintype "passive"))
      (node (ref "U1") (pin "26") (pinfunction "PD6(ADC9)_26") (pintype "bidirectional"))
    )
    (net (code "24") (name "GND") (class "Default")
      (node (ref "ANALOG_GND") (pin "1") (pinfunction "1_1") (pintype "passive"))
      (node (ref "ANALOG_GND") (pin "2") (pinfunction "2_2") (pintype "passive"))
      (node (ref "ANALOG_GND") (pin "3") (pinfunction "3_3") (pintype "passive"))
      (node (ref "ANALOG_GND") (pin "4") (pinfunction "4_4") (pintype "passive"))
      (node (ref "ANALOG_GND") (pin "5") (pinfunction "5_5") (pintype "passive"))
      (node (ref "ANALOG_GND") (pin "6") (pinfunction "6_6") (pintype "passive"))
      (node (ref "C1") (pin "2") (pinfunction "2_2") (pintype "passive"))
      (node (ref "C10") (pin "2") (pinfunction "2_2") (pintype "passive"))
      (node (ref "C11") (pin "2") (pinfunction "2_2") (pintype "passive"))
      (node (ref "C12") (pin "2") (pinfunction "2_2") (pintype "passive"))
      (node (ref "C13") (pin "2") (pinfunction "2_2") (pintype "passive"))
      (node (ref "C14") (pin "2") (pinfunction "2_2") (pintype "passive"))
      (node (ref "C2") (pin "2") (pinfunction "2_2") (pintype "passive"))
      (node (ref "C3") (pin "2") (pinfunction "2_2") (pintype "passive"))
      (node (ref "C4") (pin "2") (pinfunction "2_2") (pintype "passive"))
      (node (ref "C7") (pin "2") (pinfunction "2_2") (pintype "passive"))
      (node (ref "C8") (pin "1") (pinfunction "1_1") (pintype "passive"))
      (node (ref "C9") (pin "1") (pinfunction "1_1") (pintype "passive"))
      (node (ref "COMM_GND") (pin "1") (pinfunction "1_1") (pintype "passive"))
      (node (ref "COMM_GND") (pin "2") (pinfunction "2_2") (pintype "passive"))
      (node (ref "COMM_GND") (pin "3") (pinfunction "3_3") (pintype "passive"))
      (node (ref "COMM_GND") (pin "4") (pinfunction "4_4") (pintype "passive"))
      (node (ref "COMM_GND") (pin "5") (pinfunction "5_5") (pintype "passive"))
      (node (ref "COMM_GND") (pin "6") (pinfunction "6_6") (pintype "passive"))
      (node (ref "COMM_GND") (pin "7") (pinfunction "7_7") (pintype "passive"))
      (node (ref "D2") (pin "C") (pinfunction "C_C") (pintype "passive"))
      (node (ref "D3") (pin "C") (pinfunction "C_C") (pintype "passive"))
      (node (ref "D4") (pin "C") (pinfunction "C_C") (pintype "passive"))
      (node (ref "DIG_GND") (pin "1") (pinfunction "1_1") (pintype "passive"))
      (node (ref "DIG_GND") (pin "2") (pinfunction "2_2") (pintype "passive"))
      (node (ref "DIG_GND") (pin "3") (pinfunction "3_3") (pintype "passive"))
      (node (ref "DIG_GND") (pin "4") (pinfunction "4_4") (pintype "passive"))
      (node (ref "DIG_GND") (pin "5") (pinfunction "5_5") (pintype "passive"))
      (node (ref "DIG_GND") (pin "6") (pinfunction "6_6") (pintype "passive"))
      (node (ref "DIG_GND") (pin "7") (pinfunction "7_7") (pintype "passive"))
      (node (ref "DIG_GND") (pin "8") (pinfunction "8_8") (pintype "passive"))
      (node (ref "DIG_GND") (pin "9") (pinfunction "9_9") (pintype "passive"))
      (node (ref "ISP") (pin "6") (pinfunction "6_6") (pintype "passive"))
      (node (ref "J1") (pin "GND") (pinfunction "GND_GND") (pintype "power_in"))
      (node (ref "JP2") (pin "1") (pinfunction "1_1") (pintype "passive"))
      (node (ref "JST") (pin "1") (pinfunction "-_1") (pintype "bidirectional"))
      (node (ref "OLED1") (pin "1") (pinfunction "GND_1") (pintype "bidirectional"))
      (node (ref "OLED1") (pin "10") (pinfunction "BS2_10") (pintype "bidirectional"))
      (node (ref "OLED1") (pin "27") (pinfunction "VLSS_27") (pintype "bidirectional"))
      (node (ref "OLED1") (pin "28") (pinfunction "GND_28") (pintype "bidirectional"))
      (node (ref "OLED1") (pin "7") (pinfunction "VSS_7") (pintype "bidirectional"))
      (node (ref "PTH") (pin "2") (pinfunction "2_2") (pintype "passive"))
      (node (ref "PWR_GND") (pin "1") (pinfunction "1_1") (pintype "passive"))
      (node (ref "PWR_GND") (pin "2") (pinfunction "2_2") (pintype "passive"))
      (node (ref "PWR_GND") (pin "3") (pinfunction "3_3") (pintype "passive"))
      (node (ref "PWR_GND") (pin "4") (pinfunction "4_4") (pintype "passive"))
      (node (ref "QWIIC") (pin "1") (pinfunction "1_1") (pintype "power_in"))
      (node (ref "R13") (pin "1") (pinfunction "1_1") (pintype "passive"))
      (node (ref "S1") (pin "1") (pinfunction "O_1") (pintype "passive"))
      (node (ref "S2") (pin "3") (pinfunction "2_3") (pintype "passive"))
      (node (ref "S2") (pin "4") (pinfunction "2_4") (pintype "passive"))
      (node (ref "U1") (pin "15") (pinfunction "GND_15") (pintype "bidirectional"))
      (node (ref "U1") (pin "23") (pinfunction "GND_23") (pintype "bidirectional"))
      (node (ref "U1") (pin "33") (pinfunction "PE2/~{HWB}_33") (pintype "bidirectional"))
      (node (ref "U1") (pin "35") (pinfunction "GND_35") (pintype "bidirectional"))
      (node (ref "U1") (pin "43") (pinfunction "GND_43") (pintype "bidirectional"))
      (node (ref "U1") (pin "5") (pinfunction "UGND_5") (pintype "bidirectional"))
    )
    (net (code "25") (name "MISO") (class "Default")
      (node (ref "COMM") (pin "3") (pinfunction "3_3") (pintype "passive"))
      (node (ref "ISP") (pin "1") (pinfunction "1_1") (pintype "passive"))
      (node (ref "U1") (pin "11") (pinfunction "PB3(MISO)_11") (pintype "bidirectional"))
    )
    (net (code "26") (name "MOSI") (class "Default")
      (node (ref "COMM") (pin "2") (pinfunction "2_2") (pintype "passive"))
      (node (ref "ISP") (pin "4") (pinfunction "4_4") (pintype "passive"))
      (node (ref "U1") (pin "10") (pinfunction "PB2(MOSI)_10") (pintype "bidirectional"))
    )
    (net (code "27") (name "Net-(3.3V_REG-BP)") (class "Default")
      (node (ref "3.3V_REG") (pin "4") (pinfunction "BP_4") (pintype "input"))
      (node (ref "C1") (pin "1") (pinfunction "1_1") (pintype "passive"))
    )
    (net (code "28") (name "Net-(3.3V_REG-EN)") (class "Default")
      (node (ref "3.3V_REG") (pin "3") (pinfunction "EN_3") (pintype "input"))
      (node (ref "S1") (pin "2") (pinfunction "P_2") (pintype "passive"))
    )
    (net (code "29") (name "Net-(3.3V_REG-GND)") (class "Default")
      (node (ref "3.3V_REG") (pin "2") (pinfunction "GND_2") (pintype "input"))
      (node (ref "BAT_CHARGE") (pin "2") (pinfunction "VSS_2") (pintype "power_in"))
      (node (ref "R7") (pin "2") (pinfunction "2_2") (pintype "passive"))
    )
    (net (code "30") (name "Net-(BAT_CHARGE-PROG)") (class "Default")
      (node (ref "BAT_CHARGE") (pin "5") (pinfunction "PROG_5") (pintype "input"))
      (node (ref "R7") (pin "1") (pinfunction "1_1") (pintype "passive"))
    )
    (net (code "31") (name "Net-(BAT_CHARGE-STAT)") (class "Default")
      (node (ref "BAT_CHARGE") (pin "1") (pinfunction "STAT_1") (pintype "output"))
      (node (ref "D1") (pin "C") (pinfunction "C_C") (pintype "passive"))
    )
    (net (code "32") (name "Net-(BAT_CHARGE-VIN)") (class "Default")
      (node (ref "BAT_CHARGE") (pin "4") (pinfunction "VIN_4") (pintype "power_in"))
      (node (ref "F1") (pin "2") (pinfunction "2_2") (pintype "bidirectional"))
      (node (ref "R3") (pin "2") (pinfunction "2_2") (pintype "passive"))
    )
    (net (code "33") (name "Net-(D1-PadA)") (class "Default")
      (node (ref "D1") (pin "A") (pinfunction "A_A") (pintype "passive"))
      (node (ref "R3") (pin "1") (pinfunction "1_1") (pintype "passive"))
    )
    (net (code "34") (name "Net-(D2-PadA)") (class "Default")
      (node (ref "D2") (pin "A") (pinfunction "A_A") (pintype "passive"))
      (node (ref "R4") (pin "1") (pinfunction "1_1") (pintype "passive"))
    )
    (net (code "35") (name "Net-(D3-PadA)") (class "Default")
      (node (ref "D3") (pin "A") (pinfunction "A_A") (pintype "passive"))
      (node (ref "R5") (pin "1") (pinfunction "1_1") (pintype "passive"))
    )
    (net (code "36") (name "Net-(D4-PadA)") (class "Default")
      (node (ref "D4") (pin "A") (pinfunction "A_A") (pintype "passive"))
      (node (ref "R6") (pin "1") (pinfunction "1_1") (pintype "passive"))
    )
    (net (code "37") (name "Net-(J1-PadD+)") (class "Default")
      (node (ref "J1") (pin "D+") (pinfunction "D+_D+") (pintype "bidirectional"))
      (node (ref "R2") (pin "1") (pinfunction "1_1") (pintype "passive"))
    )
    (net (code "38") (name "Net-(J1-PadD-)") (class "Default")
      (node (ref "J1") (pin "D-") (pinfunction "D-_D-") (pintype "bidirectional"))
      (node (ref "R1") (pin "1") (pinfunction "1_1") (pintype "passive"))
    )
    (net (code "39") (name "Net-(JP1-Pad1)") (class "Default")
      (node (ref "JP1") (pin "1") (pinfunction "1_1") (pintype "passive"))
      (node (ref "R12") (pin "2") (pinfunction "2_2") (pintype "passive"))
    )
    (net (code "40") (name "Net-(JP1-Pad3)") (class "Default")
      (node (ref "JP1") (pin "3") (pinfunction "3_3") (pintype "passive"))
      (node (ref "R11") (pin "2") (pinfunction "2_2") (pintype "passive"))
    )
    (net (code "41") (name "Net-(OLED1-C1N)") (class "Default")
      (node (ref "C6") (pin "2") (pinfunction "2_2") (pintype "passive"))
      (node (ref "OLED1") (pin "5") (pinfunction "C1N_5") (pintype "bidirectional"))
    )
    (net (code "42") (name "Net-(OLED1-C1P)") (class "Default")
      (node (ref "C6") (pin "1") (pinfunction "1_1") (pintype "passive"))
      (node (ref "OLED1") (pin "4") (pinfunction "C1P_4") (pintype "bidirectional"))
    )
    (net (code "43") (name "Net-(OLED1-C2N)") (class "Default")
      (node (ref "C5") (pin "2") (pinfunction "2_2") (pintype "passive"))
      (node (ref "OLED1") (pin "3") (pinfunction "C2N_3") (pintype "bidirectional"))
    )
    (net (code "44") (name "Net-(OLED1-C2P)") (class "Default")
      (node (ref "C5") (pin "1") (pinfunction "1_1") (pintype "passive"))
      (node (ref "OLED1") (pin "2") (pinfunction "C2P_2") (pintype "bidirectional"))
    )
    (net (code "45") (name "Net-(OLED1-IREF)") (class "Default")
      (node (ref "OLED1") (pin "24") (pinfunction "IREF_24") (pintype "bidirectional"))
      (node (ref "R13") (pin "2") (pinfunction "2_2") (pintype "passive"))
    )
    (net (code "46") (name "Net-(OLED1-VCC)") (class "Default")
      (node (ref "C4") (pin "1") (pinfunction "1_1") (pintype "passive"))
      (node (ref "OLED1") (pin "26") (pinfunction "VCC_26") (pintype "bidirectional"))
    )
    (net (code "47") (name "Net-(OLED1-VCOMH)") (class "Default")
      (node (ref "C3") (pin "1") (pinfunction "1_1") (pintype "passive"))
      (node (ref "OLED1") (pin "25") (pinfunction "VCOMH_25") (pintype "bidirectional"))
    )
    (net (code "48") (name "Net-(OLED1-~{RESET})") (class "Default")
      (node (ref "C7") (pin "1") (pinfunction "1_1") (pintype "passive"))
      (node (ref "OLED1") (pin "12") (pinfunction "~{RESET}_12") (pintype "bidirectional"))
      (node (ref "R8") (pin "1") (pinfunction "1_1") (pintype "passive"))
    )
    (net (code "49") (name "Net-(U1-AREF)") (class "Default")
      (node (ref "C11") (pin "1") (pinfunction "1_1") (pintype "passive"))
      (node (ref "U1") (pin "42") (pinfunction "AREF_42") (pintype "bidirectional"))
    )
    (net (code "50") (name "Net-(U1-PB0(SS))") (class "Default")
      (node (ref "R5") (pin "2") (pinfunction "2_2") (pintype "passive"))
      (node (ref "U1") (pin "8") (pinfunction "PB0(SS)_8") (pintype "bidirectional"))
    )
    (net (code "51") (name "Net-(U1-PC7)") (class "Default")
      (node (ref "R6") (pin "2") (pinfunction "2_2") (pintype "passive"))
      (node (ref "U1") (pin "32") (pinfunction "PC7_32") (pintype "bidirectional"))
    )
    (net (code "52") (name "Net-(U1-PD5)") (class "Default")
      (node (ref "R4") (pin "2") (pinfunction "2_2") (pintype "passive"))
      (node (ref "U1") (pin "22") (pinfunction "PD5_22") (pintype "bidirectional"))
    )
    (net (code "53") (name "Net-(U1-UCAP)") (class "Default")
      (node (ref "C10") (pin "1") (pinfunction "1_1") (pintype "passive"))
      (node (ref "U1") (pin "6") (pinfunction "UCAP_6") (pintype "bidirectional"))
    )
    (net (code "54") (name "Net-(U1-XTAL1)") (class "Default")
      (node (ref "C9") (pin "2") (pinfunction "2_2") (pintype "passive"))
      (node (ref "U1") (pin "17") (pinfunction "XTAL1_17") (pintype "bidirectional"))
      (node (ref "Y1") (pin "3") (pinfunction "2_3") (pintype "passive"))
    )
    (net (code "55") (name "Net-(U1-XTAL2)") (class "Default")
      (node (ref "C8") (pin "2") (pinfunction "2_2") (pintype "passive"))
      (node (ref "U1") (pin "16") (pinfunction "XTAL2_16") (pintype "bidirectional"))
      (node (ref "Y1") (pin "1") (pinfunction "1_1") (pintype "passive"))
    )
    (net (code "56") (name "O_D3") (class "Default")
      (node (ref "OLED1") (pin "19") (pinfunction "D3_19") (pintype "bidirectional"))
    )
    (net (code "57") (name "O_D4") (class "Default")
      (node (ref "OLED1") (pin "20") (pinfunction "D4_20") (pintype "bidirectional"))
    )
    (net (code "58") (name "O_D5") (class "Default")
      (node (ref "OLED1") (pin "21") (pinfunction "D5_21") (pintype "bidirectional"))
    )
    (net (code "59") (name "O_D6") (class "Default")
      (node (ref "OLED1") (pin "22") (pinfunction "D6_22") (pintype "bidirectional"))
    )
    (net (code "60") (name "O_D7") (class "Default")
      (node (ref "OLED1") (pin "23") (pinfunction "D7_23") (pintype "bidirectional"))
    )
    (net (code "61") (name "RAW") (class "Default")
      (node (ref "3.3V_REG") (pin "1") (pinfunction "IN_1") (pintype "input"))
      (node (ref "D5") (pin "C") (pinfunction "C_C") (pintype "passive"))
      (node (ref "PWR") (pin "4") (pinfunction "4_4") (pintype "passive"))
    )
    (net (code "62") (name "RXI") (class "Default")
      (node (ref "COMM") (pin "4") (pinfunction "4_4") (pintype "passive"))
      (node (ref "U1") (pin "20") (pinfunction "PD2(RX)_20") (pintype "bidirectional"))
    )
    (net (code "63") (name "SCK") (class "Default")
      (node (ref "COMM") (pin "1") (pinfunction "1_1") (pintype "passive"))
      (node (ref "ISP") (pin "3") (pinfunction "3_3") (pintype "passive"))
      (node (ref "U1") (pin "9") (pinfunction "PB1(SCK)_9") (pintype "bidirectional"))
    )
    (net (code "64") (name "SCL") (class "Default")
      (node (ref "COMM") (pin "7") (pinfunction "7_7") (pintype "passive"))
      (node (ref "OLED1") (pin "16") (pinfunction "D0/SCK_16") (pintype "bidirectional"))
      (node (ref "QWIIC") (pin "4") (pinfunction "4_4") (pintype "passive"))
      (node (ref "R12") (pin "1") (pinfunction "1_1") (pintype "passive"))
      (node (ref "U1") (pin "18") (pinfunction "PD0(SCL)_18") (pintype "bidirectional"))
    )
    (net (code "65") (name "SDA") (class "Default")
      (node (ref "COMM") (pin "6") (pinfunction "6_6") (pintype "passive"))
      (node (ref "OLED1") (pin "17") (pinfunction "D1/MOSI_17") (pintype "bidirectional"))
      (node (ref "OLED1") (pin "18") (pinfunction "D2_18") (pintype "bidirectional"))
      (node (ref "QWIIC") (pin "3") (pinfunction "3_3") (pintype "passive"))
      (node (ref "R11") (pin "1") (pinfunction "1_1") (pintype "passive"))
      (node (ref "U1") (pin "19") (pinfunction "PD1(SDA)_19") (pintype "bidirectional"))
    )
    (net (code "66") (name "SHIELD") (class "Default")
      (node (ref "J1") (pin "SHIELD1") (pinfunction "SHIELD_SHIELD1") (pintype "bidirectional"))
      (node (ref "J1") (pin "SHIELD2") (pinfunction "SHIELD_SHIELD2") (pintype "bidirectional"))
      (node (ref "J1") (pin "SHIELD3") (pinfunction "SHIELD_SHIELD3") (pintype "bidirectional"))
    )
    (net (code "67") (name "TXO") (class "Default")
      (node (ref "COMM") (pin "5") (pinfunction "5_5") (pintype "passive"))
      (node (ref "U1") (pin "21") (pinfunction "PD3(TX)_21") (pintype "bidirectional"))
    )
    (net (code "68") (name "V_BAT") (class "Default")
      (node (ref "BAT_CHARGE") (pin "3") (pinfunction "VBAT_3") (pintype "power_in"))
      (node (ref "C12") (pin "1") (pinfunction "1_1") (pintype "passive"))
      (node (ref "D5") (pin "A") (pinfunction "A_A") (pintype "passive"))
      (node (ref "JST") (pin "2") (pinfunction "+_2") (pintype "bidirectional"))
      (node (ref "PTH") (pin "1") (pinfunction "1_1") (pintype "passive"))
    )
    (net (code "69") (name "V_USB") (class "Default")
      (node (ref "C13") (pin "1") (pinfunction "1_1") (pintype "passive"))
      (node (ref "F1") (pin "1") (pinfunction "1_1") (pintype "bidirectional"))
      (node (ref "J1") (pin "VBUS") (pinfunction "VBUS_VBUS") (pintype "power_in"))
      (node (ref "S1") (pin "3") (pinfunction "S_3") (pintype "passive"))
      (node (ref "U1") (pin "2") (pinfunction "UVCC_2") (pintype "bidirectional"))
      (node (ref "U1") (pin "7") (pinfunction "VBUS_7") (pintype "bidirectional"))
    )
    (net (code "70") (name "unconnected-(J1-PadID)") (class "Default")
      (node (ref "J1") (pin "ID") (pinfunction "ID_ID") (pintype "bidirectional"))
    )
    (net (code "71") (name "unconnected-(JST-PAD1-PadNC1)") (class "Default")
      (node (ref "JST") (pin "NC1") (pinfunction "PAD1_NC1") (pintype "bidirectional"))
    )
    (net (code "72") (name "unconnected-(JST-PAD2-PadNC2)") (class "Default")
      (node (ref "JST") (pin "NC2") (pinfunction "PAD2_NC2") (pintype "bidirectional"))
    )
  )
)
